# Prototype.net
KiCad netlist of a schematic drawn in EAGLE
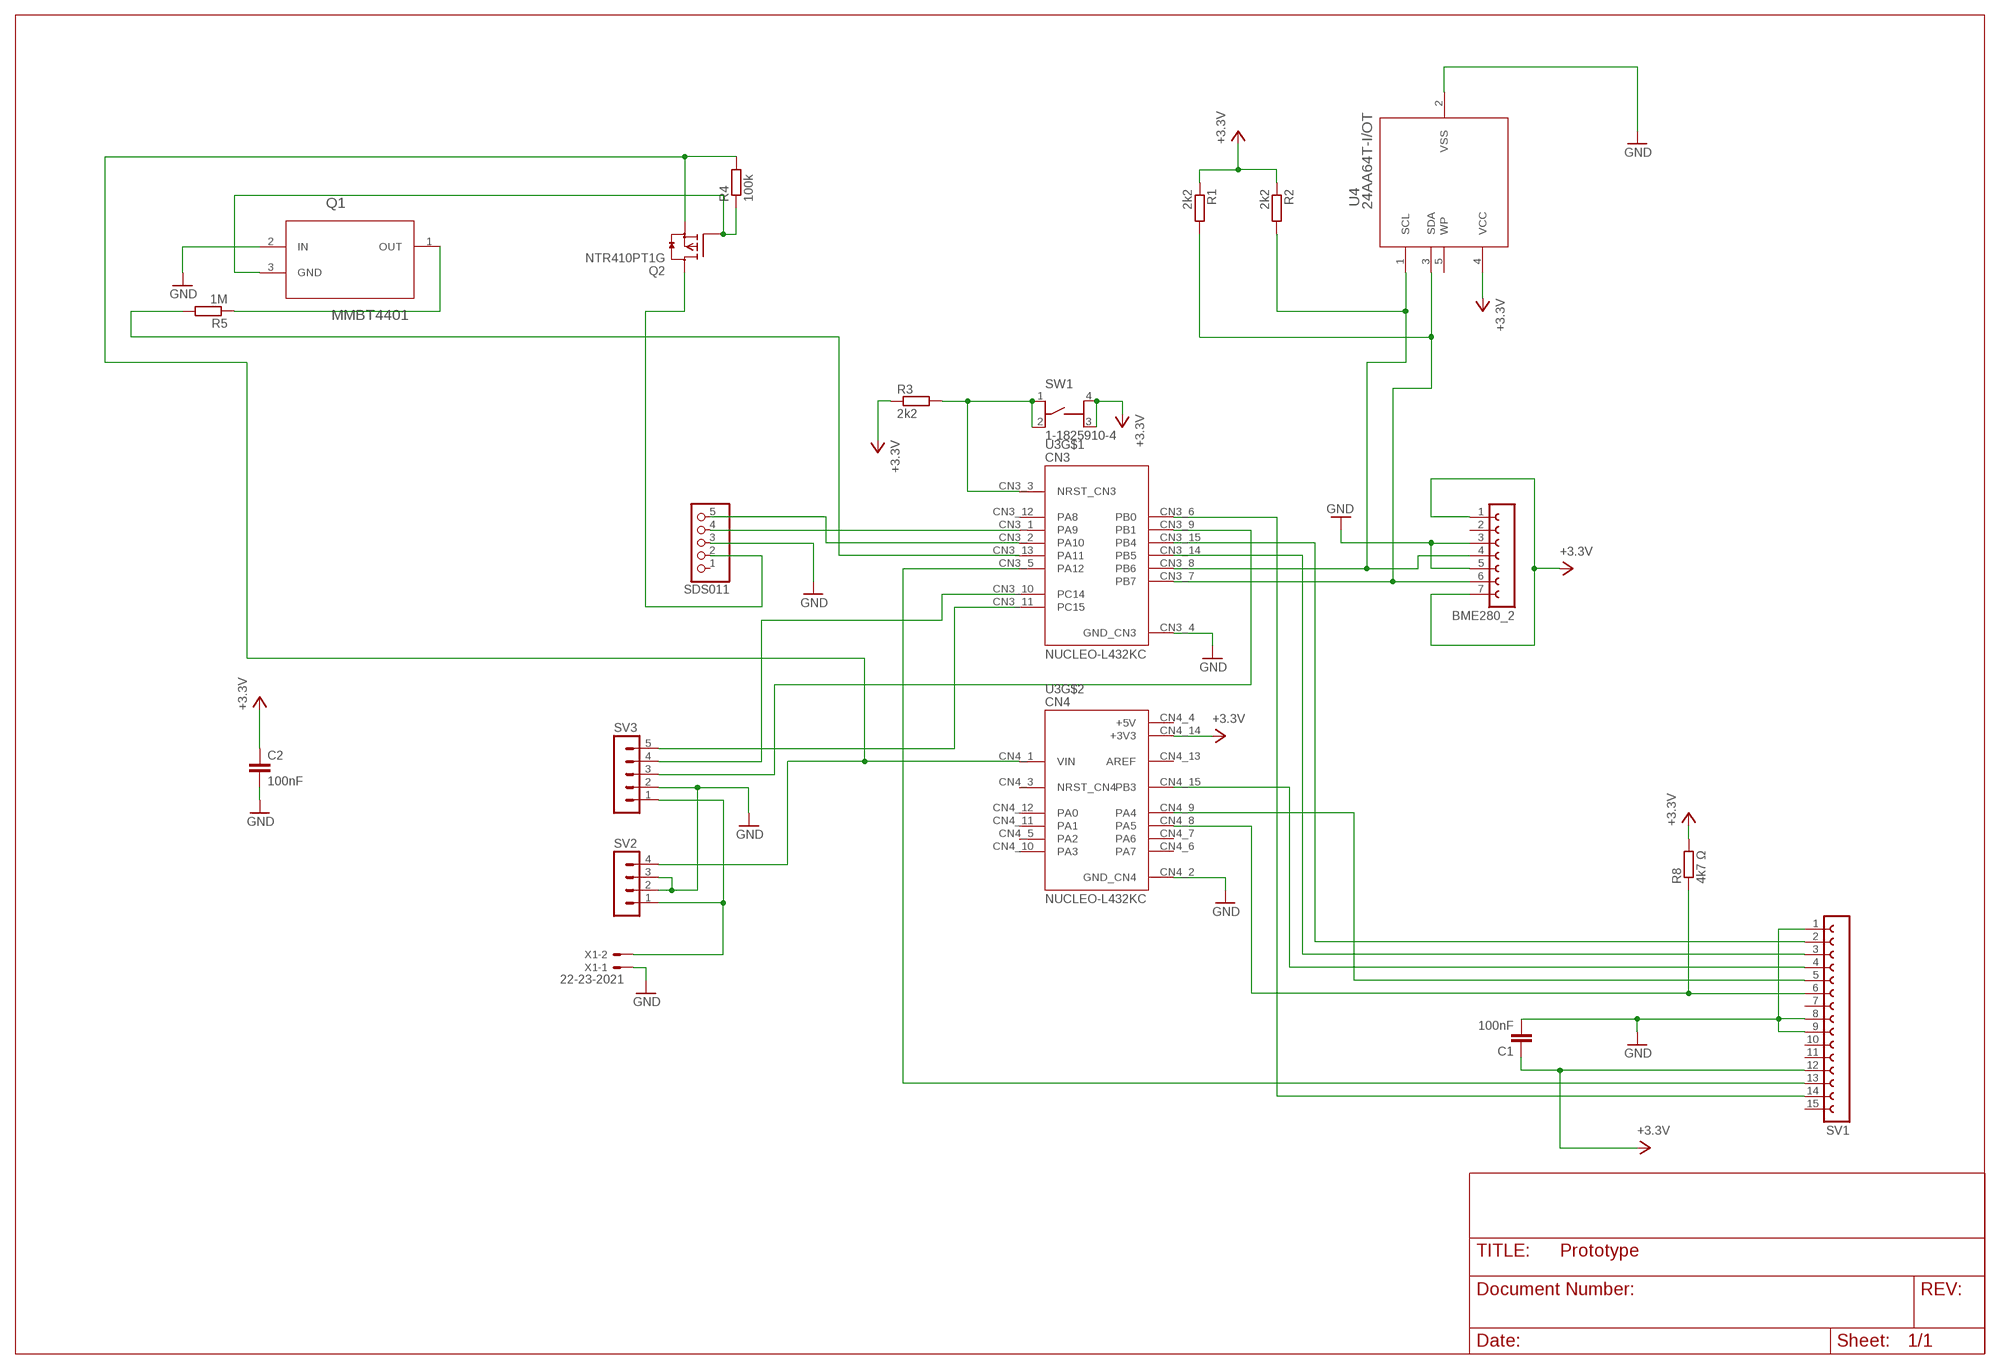
[diagram p0: schematic, sheet 1]

(export (version "E")
  (design (tool "Eeschema 10.0.6"))
  (components
    (comp (ref "BME280_2")
      (value "FE07-1")
      (footprint "eagle-import:FE07")
      (libsource (lib "eagle-import") (part "FE07-1"))
    )
    (comp (ref "C1")
      (value "100nF")
      (footprint "eagle-import:C0603K")
      (libsource (lib "eagle-import") (part "C-EUC0603K"))
    )
    (comp (ref "C2")
      (value "100nF")
      (footprint "eagle-import:C0603K")
      (libsource (lib "eagle-import") (part "C-EUC0603K"))
    )
    (comp (ref "Q1")
      (value "MMBT4401")
      (footprint "eagle-import:SOT95P263X110-3N")
      (fields (field (name "MF") "Texas Instruments") (field (name "MP") "LM3480IM3-5.0"))
      (libsource (lib "eagle-import") (part "LM3480IM3-5.0"))
    )
    (comp (ref "Q2")
      (value "NTR410PT1G")
      (footprint "eagle-import:SOT23")
      (fields (field (name "MF") "ON Semiconductor") (field (name "MP") "BSS84LT1"))
      (libsource (lib "eagle-import") (part "BSS84LT1"))
    )
    (comp (ref "R1")
      (value "2k2")
      (footprint "eagle-import:R1206W")
      (libsource (lib "eagle-import") (part "R-EU_R1206W"))
    )
    (comp (ref "R2")
      (value "2k2")
      (footprint "eagle-import:R1206W")
      (libsource (lib "eagle-import") (part "R-EU_R1206W"))
    )
    (comp (ref "R3")
      (value "2k2")
      (footprint "eagle-import:R1206W")
      (libsource (lib "eagle-import") (part "R-EU_R1206W"))
    )
    (comp (ref "R4")
      (value "100k")
      (footprint "eagle-import:R1206W")
      (libsource (lib "eagle-import") (part "R-EU_R1206W"))
    )
    (comp (ref "R5")
      (value "1M")
      (footprint "eagle-import:R1206W")
      (libsource (lib "eagle-import") (part "R-EU_R1206W"))
    )
    (comp (ref "R8")
      (value "4k7 Ω")
      (footprint "eagle-import:R1206W")
      (libsource (lib "eagle-import") (part "R-EU_R1206W"))
    )
    (comp (ref "SDS011")
      (value "PINHD-1X5")
      (footprint "eagle-import:1X05")
      (libsource (lib "eagle-import") (part "PINHD-1X5"))
    )
    (comp (ref "SV1")
      (value "FE15-1")
      (footprint "eagle-import:FE15")
      (libsource (lib "eagle-import") (part "FE15-1"))
    )
    (comp (ref "SV2")
      (value "MA04-1")
      (footprint "eagle-import:MA04-1")
      (libsource (lib "eagle-import") (part "MA04-1"))
    )
    (comp (ref "SV3")
      (value "MA05-1")
      (footprint "eagle-import:MA05-1")
      (libsource (lib "eagle-import") (part "MA05-1"))
    )
    (comp (ref "SW1")
      (value "1-1825910-4")
      (footprint "eagle-import:TE_1-1825910-4")
      (fields (field (name "MF") "TE Connectivity") (field (name "MP") "118259104"))
      (libsource (lib "eagle-import") (part "1-1825910-4"))
    )
    (comp (ref "U3")
      (value "NUCLEO-L432KC")
      (footprint "eagle-import:MODULE_NUCLEO-L432KC")
      (fields (field (name "MF") "STMicroelectronics"))
      (libsource (lib "eagle-import") (part "NUCLEO-L432KC"))
    )
    (comp (ref "U4")
      (value "24AA64T-I/OT")
      (footprint "eagle-import:SOT-23-5_MC")
      (fields (field (name "COPYRIGHT") "Copyright (C) 2018 Accelerated Designs. All rights reserved"))
      (libsource (lib "eagle-import") (part "24AA64T-I/OT"))
    )
    (comp (ref "X1")
      (value "22-23-2021")
      (footprint "eagle-import:22-23-2021")
      (fields (field (name "MF") "MOLEX"))
      (libsource (lib "eagle-import") (part "22-23-2021"))
    )
  )
  (nets
    (net (code "1") (name "+3.3V") (class "Default")
      (node (ref "BME280_2") (pin "1") (pinfunction "1_1") (pintype "passive"))
      (node (ref "BME280_2") (pin "7") (pinfunction "7_7") (pintype "passive"))
      (node (ref "C1") (pin "1") (pinfunction "1_1") (pintype "passive"))
      (node (ref "C2") (pin "1") (pinfunction "1_1") (pintype "passive"))
      (node (ref "R1") (pin "1") (pinfunction "1_1") (pintype "passive"))
      (node (ref "R2") (pin "1") (pinfunction "1_1") (pintype "passive"))
      (node (ref "R3") (pin "1") (pinfunction "1_1") (pintype "passive"))
      (node (ref "R8") (pin "2") (pinfunction "2_2") (pintype "passive"))
      (node (ref "SV1") (pin "12") (pinfunction "12_12") (pintype "passive"))
      (node (ref "SW1") (pin "3") (pinfunction "3_3") (pintype "passive"))
      (node (ref "SW1") (pin "4") (pinfunction "4_4") (pintype "passive"))
      (node (ref "U3") (pin "CN4_14") (pinfunction "+3V3_CN4_14") (pintype "power_in"))
      (node (ref "U4") (pin "4") (pinfunction "VCC_4") (pintype "power_in"))
    )
    (net (code "2") (name "/+5V") (class "Default")
      (node (ref "U3") (pin "CN4_4") (pinfunction "+5V_CN4_4") (pintype "power_in"))
    )
    (net (code "3") (name "GND") (class "Default")
      (node (ref "BME280_2") (pin "3") (pinfunction "3_3") (pintype "passive"))
      (node (ref "BME280_2") (pin "5") (pinfunction "5_5") (pintype "passive"))
      (node (ref "C1") (pin "2") (pinfunction "2_2") (pintype "passive"))
      (node (ref "C2") (pin "2") (pinfunction "2_2") (pintype "passive"))
      (node (ref "Q1") (pin "2") (pinfunction "IN_2") (pintype "power_in"))
      (node (ref "SDS011") (pin "3") (pinfunction "3_3") (pintype "passive"))
      (node (ref "SV1") (pin "1") (pinfunction "1_1") (pintype "passive"))
      (node (ref "SV1") (pin "8") (pinfunction "8_8") (pintype "passive"))
      (node (ref "SV1") (pin "9") (pinfunction "9_9") (pintype "passive"))
      (node (ref "SV2") (pin "2") (pinfunction "2_2") (pintype "passive"))
      (node (ref "SV2") (pin "3") (pinfunction "3_3") (pintype "passive"))
      (node (ref "SV3") (pin "2") (pinfunction "2_2") (pintype "passive"))
      (node (ref "U3") (pin "CN3_4") (pinfunction "GND_CN3_CN3_4") (pintype "power_in"))
      (node (ref "U3") (pin "CN4_2") (pinfunction "GND_CN4_CN4_2") (pintype "power_in"))
      (node (ref "U4") (pin "2") (pinfunction "VSS_2") (pintype "power_in"))
      (node (ref "X1") (pin "1") (pinfunction "S_1") (pintype "passive"))
    )
    (net (code "4") (name "Net-(Q1-GND)") (class "Default")
      (node (ref "Q1") (pin "3") (pinfunction "GND_3") (pintype "passive"))
      (node (ref "Q2") (pin "1") (pinfunction "G_1") (pintype "passive"))
      (node (ref "R4") (pin "1") (pinfunction "1_1") (pintype "passive"))
    )
    (net (code "5") (name "Net-(Q1-OUT)") (class "Default")
      (node (ref "Q1") (pin "1") (pinfunction "OUT_1") (pintype "output"))
      (node (ref "R5") (pin "1") (pinfunction "1_1") (pintype "passive"))
    )
    (net (code "6") (name "Net-(Q2-D)") (class "Default")
      (node (ref "Q2") (pin "3") (pinfunction "D_3") (pintype "passive"))
      (node (ref "SDS011") (pin "2") (pinfunction "2_2") (pintype "passive"))
    )
    (net (code "7") (name "Net-(Q2-S)") (class "Default")
      (node (ref "Q2") (pin "2") (pinfunction "S_2") (pintype "passive"))
      (node (ref "R4") (pin "2") (pinfunction "2_2") (pintype "passive"))
      (node (ref "SV2") (pin "4") (pinfunction "4_4") (pintype "passive"))
      (node (ref "U3") (pin "CN4_1") (pinfunction "VIN_CN4_1") (pintype "input"))
    )
    (net (code "8") (name "Net-(U3A-NRST_CN3)") (class "Default")
      (node (ref "R3") (pin "2") (pinfunction "2_2") (pintype "passive"))
      (node (ref "SW1") (pin "1") (pinfunction "1_1") (pintype "passive"))
      (node (ref "SW1") (pin "2") (pinfunction "2_2") (pintype "passive"))
      (node (ref "U3") (pin "CN3_3") (pinfunction "NRST_CN3_CN3_3") (pintype "bidirectional"))
    )
    (net (code "9") (name "Net-(U3A-PA9)") (class "Default")
      (node (ref "SDS011") (pin "4") (pinfunction "4_4") (pintype "passive"))
      (node (ref "U3") (pin "CN3_1") (pinfunction "PA9_CN3_1") (pintype "bidirectional"))
    )
    (net (code "10") (name "Net-(U3A-PA10)") (class "Default")
      (node (ref "SDS011") (pin "5") (pinfunction "5_5") (pintype "passive"))
      (node (ref "U3") (pin "CN3_2") (pinfunction "PA10_CN3_2") (pintype "bidirectional"))
    )
    (net (code "11") (name "Net-(U3A-PA11)") (class "Default")
      (node (ref "R5") (pin "2") (pinfunction "2_2") (pintype "passive"))
      (node (ref "U3") (pin "CN3_13") (pinfunction "PA11_CN3_13") (pintype "bidirectional"))
    )
    (net (code "12") (name "Net-(U3A-PA12)") (class "Default")
      (node (ref "SV1") (pin "13") (pinfunction "13_13") (pintype "passive"))
      (node (ref "U3") (pin "CN3_5") (pinfunction "PA12_CN3_5") (pintype "bidirectional"))
    )
    (net (code "13") (name "Net-(U3A-PB0)") (class "Default")
      (node (ref "SV1") (pin "14") (pinfunction "14_14") (pintype "passive"))
      (node (ref "U3") (pin "CN3_6") (pinfunction "PB0_CN3_6") (pintype "bidirectional"))
    )
    (net (code "14") (name "Net-(U3A-PB1)") (class "Default")
      (node (ref "SV3") (pin "3") (pinfunction "3_3") (pintype "passive"))
      (node (ref "U3") (pin "CN3_9") (pinfunction "PB1_CN3_9") (pintype "bidirectional"))
    )
    (net (code "15") (name "Net-(U3A-PB4)") (class "Default")
      (node (ref "SV1") (pin "2") (pinfunction "2_2") (pintype "passive"))
      (node (ref "U3") (pin "CN3_15") (pinfunction "PB4_CN3_15") (pintype "bidirectional"))
    )
    (net (code "16") (name "Net-(U3A-PB5)") (class "Default")
      (node (ref "SV1") (pin "3") (pinfunction "3_3") (pintype "passive"))
      (node (ref "U3") (pin "CN3_14") (pinfunction "PB5_CN3_14") (pintype "bidirectional"))
    )
    (net (code "17") (name "Net-(U3A-PB6)") (class "Default")
      (node (ref "BME280_2") (pin "4") (pinfunction "4_4") (pintype "passive"))
      (node (ref "R2") (pin "2") (pinfunction "2_2") (pintype "passive"))
      (node (ref "U3") (pin "CN3_8") (pinfunction "PB6_CN3_8") (pintype "bidirectional"))
      (node (ref "U4") (pin "1") (pinfunction "SCL_1") (pintype "input"))
    )
    (net (code "18") (name "Net-(U3A-PB7)") (class "Default")
      (node (ref "BME280_2") (pin "6") (pinfunction "6_6") (pintype "passive"))
      (node (ref "R1") (pin "2") (pinfunction "2_2") (pintype "passive"))
      (node (ref "U3") (pin "CN3_7") (pinfunction "PB7_CN3_7") (pintype "bidirectional"))
      (node (ref "U4") (pin "3") (pinfunction "SDA_3") (pintype "bidirectional"))
    )
    (net (code "19") (name "Net-(U3A-PC14)") (class "Default")
      (node (ref "SV3") (pin "4") (pinfunction "4_4") (pintype "passive"))
      (node (ref "U3") (pin "CN3_10") (pinfunction "PC14_CN3_10") (pintype "bidirectional"))
    )
    (net (code "20") (name "Net-(U3A-PC15)") (class "Default")
      (node (ref "SV3") (pin "5") (pinfunction "5_5") (pintype "passive"))
      (node (ref "U3") (pin "CN3_11") (pinfunction "PC15_CN3_11") (pintype "bidirectional"))
    )
    (net (code "21") (name "Net-(U3B-PA4)") (class "Default")
      (node (ref "SV1") (pin "5") (pinfunction "5_5") (pintype "passive"))
      (node (ref "U3") (pin "CN4_9") (pinfunction "PA4_CN4_9") (pintype "bidirectional"))
    )
    (net (code "22") (name "Net-(U3B-PA5)") (class "Default")
      (node (ref "R8") (pin "1") (pinfunction "1_1") (pintype "passive"))
      (node (ref "SV1") (pin "6") (pinfunction "6_6") (pintype "passive"))
      (node (ref "U3") (pin "CN4_8") (pinfunction "PA5_CN4_8") (pintype "bidirectional"))
    )
    (net (code "23") (name "Net-(U3B-PB3)") (class "Default")
      (node (ref "SV1") (pin "4") (pinfunction "4_4") (pintype "passive"))
      (node (ref "U3") (pin "CN4_15") (pinfunction "PB3_CN4_15") (pintype "bidirectional"))
    )
    (net (code "24") (name "Net-(X1B-S)") (class "Default")
      (node (ref "SV2") (pin "1") (pinfunction "1_1") (pintype "passive"))
      (node (ref "SV3") (pin "1") (pinfunction "1_1") (pintype "passive"))
      (node (ref "X1") (pin "2") (pinfunction "S_2") (pintype "passive"))
    )
    (net (code "25") (name "unconnected-(BME280_2-Pad2)") (class "Default")
      (node (ref "BME280_2") (pin "2") (pinfunction "2_2") (pintype "passive"))
    )
    (net (code "26") (name "unconnected-(SDS011-Pad1)") (class "Default")
      (node (ref "SDS011") (pin "1") (pinfunction "1_1") (pintype "passive"))
    )
    (net (code "27") (name "unconnected-(SV1-Pad7)") (class "Default")
      (node (ref "SV1") (pin "7") (pinfunction "7_7") (pintype "passive"))
    )
    (net (code "28") (name "unconnected-(SV1-Pad10)") (class "Default")
      (node (ref "SV1") (pin "10") (pinfunction "10_10") (pintype "passive"))
    )
    (net (code "29") (name "unconnected-(SV1-Pad11)") (class "Default")
      (node (ref "SV1") (pin "11") (pinfunction "11_11") (pintype "passive"))
    )
    (net (code "30") (name "unconnected-(SV1-Pad15)") (class "Default")
      (node (ref "SV1") (pin "15") (pinfunction "15_15") (pintype "passive"))
    )
    (net (code "31") (name "unconnected-(U3A-PA8-PadCN3_12)") (class "Default")
      (node (ref "U3") (pin "CN3_12") (pinfunction "PA8_CN3_12") (pintype "bidirectional"))
    )
    (net (code "32") (name "unconnected-(U3B-AREF-PadCN4_13)") (class "Default")
      (node (ref "U3") (pin "CN4_13") (pinfunction "AREF_CN4_13") (pintype "bidirectional"))
    )
    (net (code "33") (name "unconnected-(U3B-NRST_CN4-PadCN4_3)") (class "Default")
      (node (ref "U3") (pin "CN4_3") (pinfunction "NRST_CN4_CN4_3") (pintype "bidirectional"))
    )
    (net (code "34") (name "unconnected-(U3B-PA0-PadCN4_12)") (class "Default")
      (node (ref "U3") (pin "CN4_12") (pinfunction "PA0_CN4_12") (pintype "bidirectional"))
    )
    (net (code "35") (name "unconnected-(U3B-PA1-PadCN4_11)") (class "Default")
      (node (ref "U3") (pin "CN4_11") (pinfunction "PA1_CN4_11") (pintype "bidirectional"))
    )
    (net (code "36") (name "unconnected-(U3B-PA2-PadCN4_5)") (class "Default")
      (node (ref "U3") (pin "CN4_5") (pinfunction "PA2_CN4_5") (pintype "bidirectional"))
    )
    (net (code "37") (name "unconnected-(U3B-PA3-PadCN4_10)") (class "Default")
      (node (ref "U3") (pin "CN4_10") (pinfunction "PA3_CN4_10") (pintype "bidirectional"))
    )
    (net (code "38") (name "unconnected-(U3B-PA6-PadCN4_7)") (class "Default")
      (node (ref "U3") (pin "CN4_7") (pinfunction "PA6_CN4_7") (pintype "bidirectional"))
    )
    (net (code "39") (name "unconnected-(U3B-PA7-PadCN4_6)") (class "Default")
      (node (ref "U3") (pin "CN4_6") (pinfunction "PA7_CN4_6") (pintype "bidirectional"))
    )
    (net (code "40") (name "unconnected-(U4-WP-Pad5)") (class "Default")
      (node (ref "U4") (pin "5") (pinfunction "WP_5") (pintype "passive"))
    )
  )
)
